# TAH_BOARD_VER_4_0.net
KiCad netlist of a schematic drawn in EAGLE
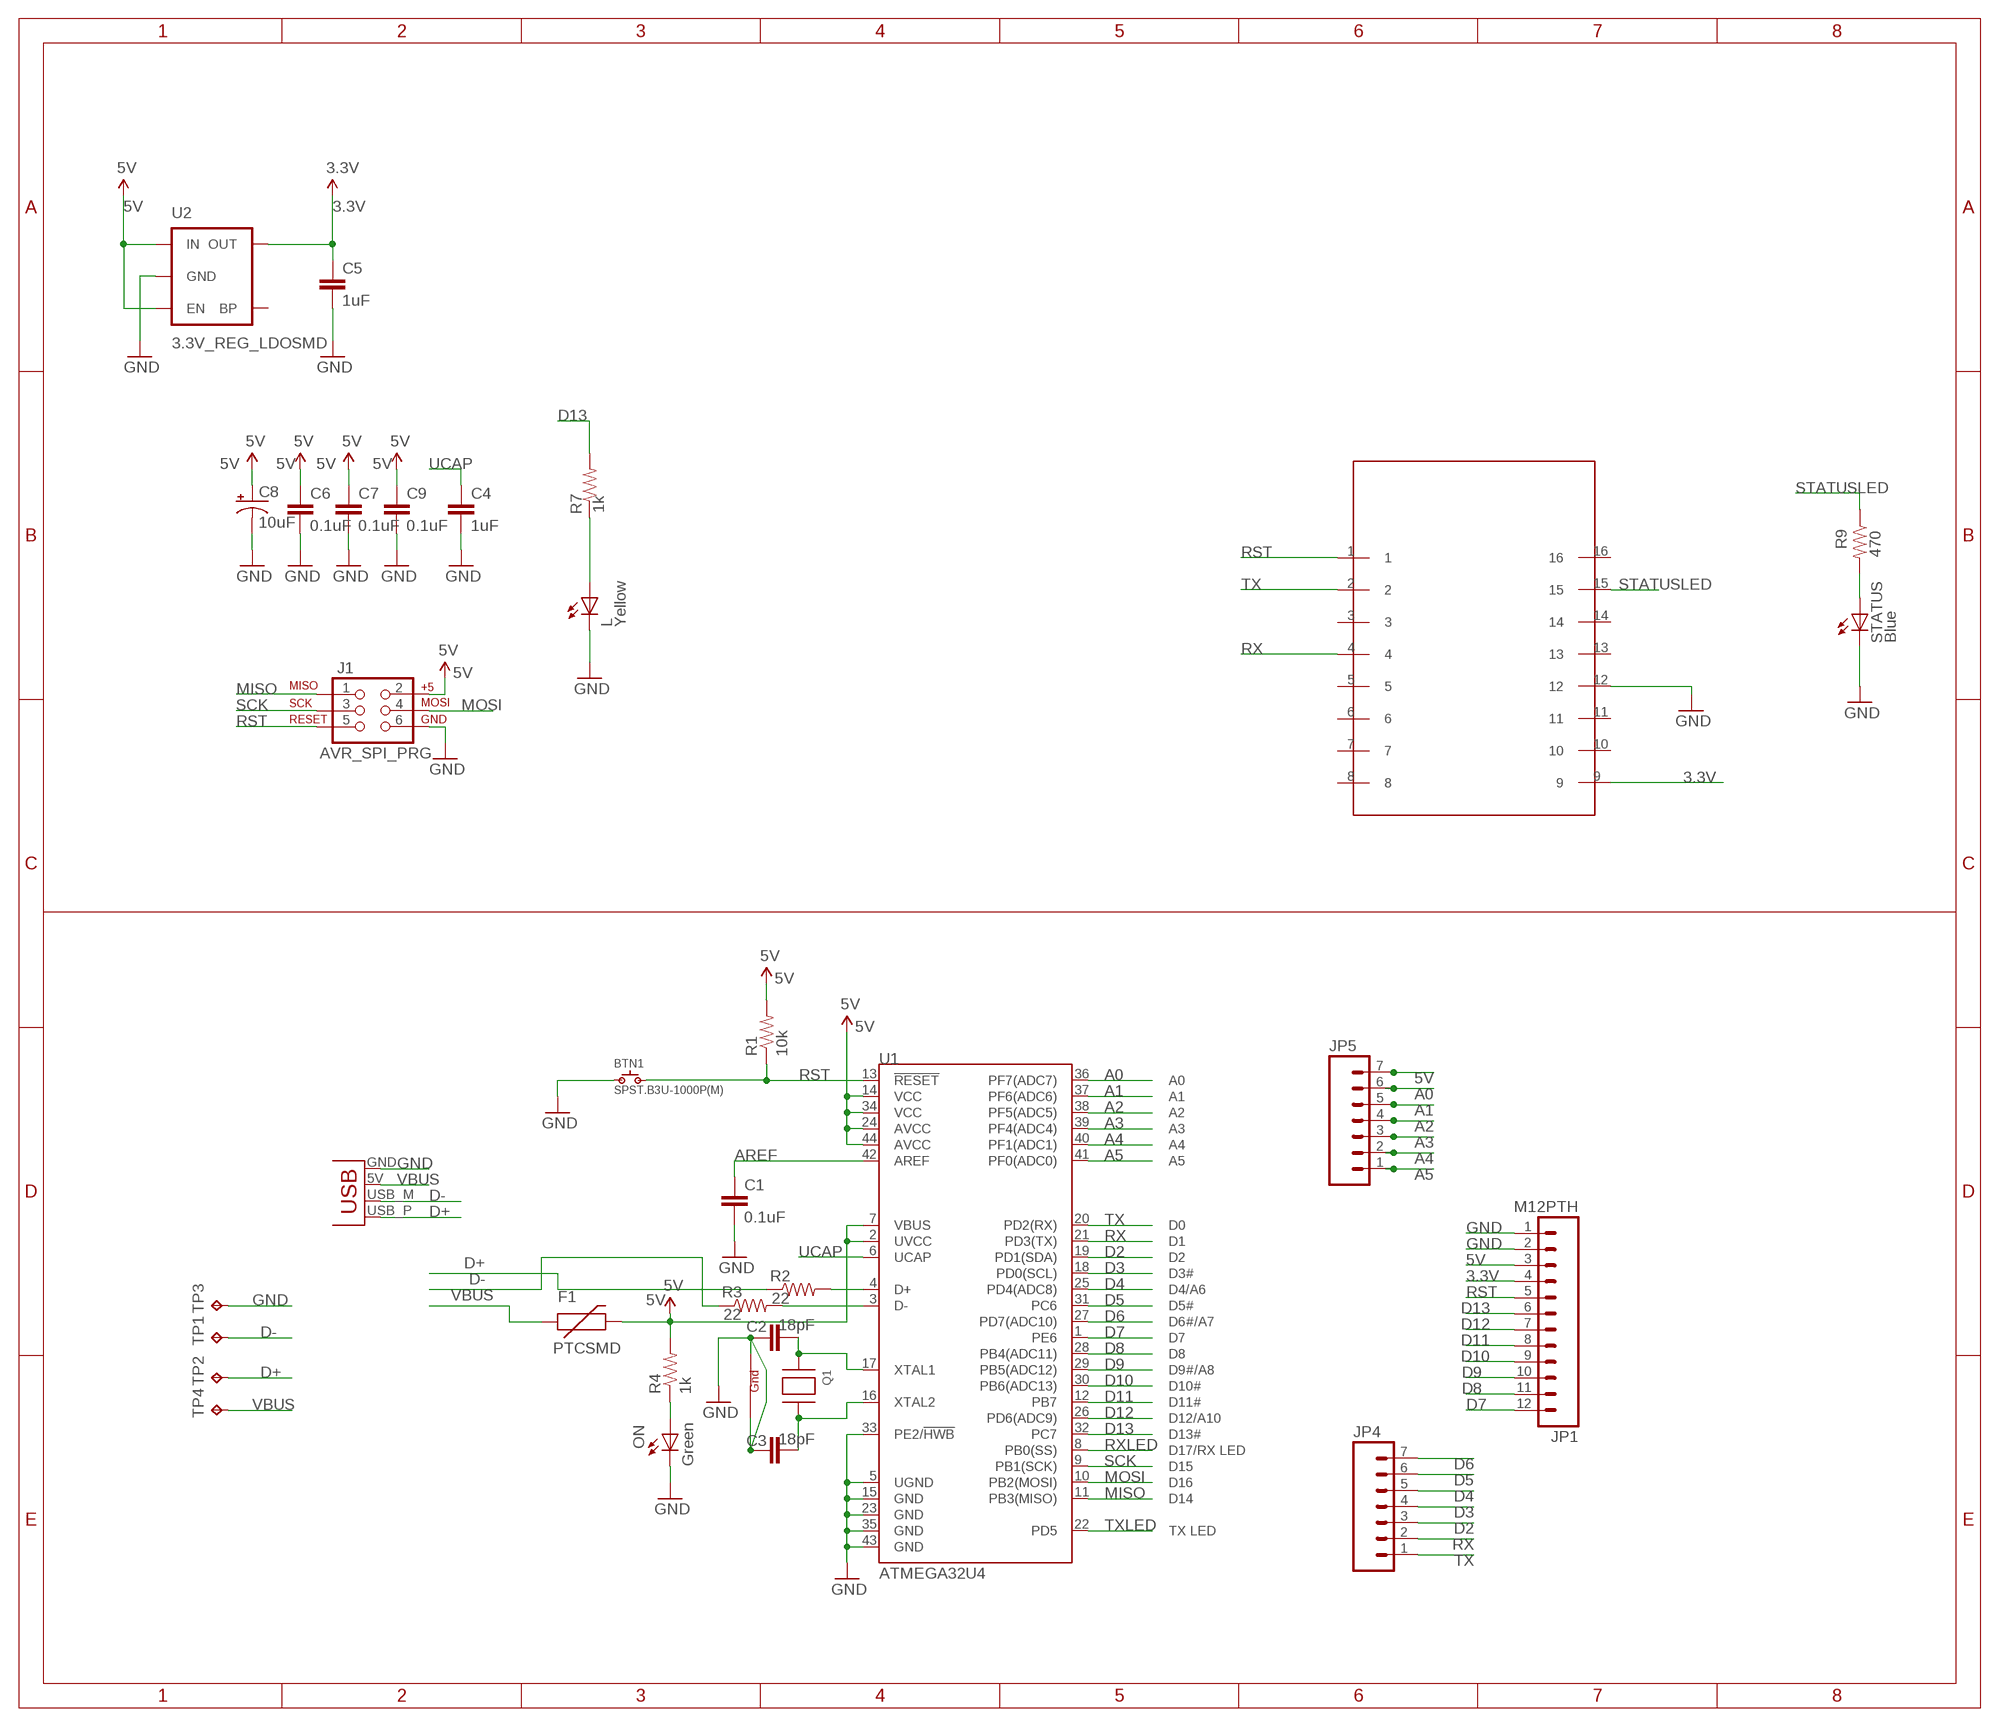
[diagram p0: schematic, sheet 1]

(export (version "E")
  (design (tool "Eeschema 10.0.6"))
  (components
    (comp (ref "BLE")
      (value "HM-11HM11")
      (footprint "eagle-import:BC05B-SMD")
      (libsource (lib "eagle-import") (part "HM-11HM11"))
    )
    (comp (ref "BTN1")
      (value "SPST.B3U-1000P(M)")
      (footprint "eagle-import:B3U-1000P(M)")
      (libsource (lib "eagle-import") (part "SPST.B3U-1000P(M)"))
    )
    (comp (ref "C1")
      (value "0.1uF")
      (footprint "eagle-import:1206")
      (libsource (lib "eagle-import") (part "2.2UF-CERCAP-10009"))
    )
    (comp (ref "C2")
      (value "18pF")
      (footprint "eagle-import:1206")
      (libsource (lib "eagle-import") (part "2.2UF-CERCAP-10009"))
    )
    (comp (ref "C3")
      (value "18pF")
      (footprint "eagle-import:1206")
      (libsource (lib "eagle-import") (part "2.2UF-CERCAP-10009"))
    )
    (comp (ref "C4")
      (value "1uF")
      (footprint "eagle-import:1206")
      (libsource (lib "eagle-import") (part "2.2UF-CERCAP-10009"))
    )
    (comp (ref "C5")
      (value "1uF")
      (footprint "eagle-import:1206")
      (libsource (lib "eagle-import") (part "2.2UF-CERCAP-10009"))
    )
    (comp (ref "C6")
      (value "0.1uF")
      (footprint "eagle-import:1206")
      (libsource (lib "eagle-import") (part "2.2UF-CERCAP-10009"))
    )
    (comp (ref "C7")
      (value "0.1uF")
      (footprint "eagle-import:1206")
      (libsource (lib "eagle-import") (part "2.2UF-CERCAP-10009"))
    )
    (comp (ref "C8")
      (value "10uF")
      (footprint "eagle-import:EIA3216")
      (libsource (lib "eagle-import") (part "CAP_POL1206"))
    )
    (comp (ref "C9")
      (value "0.1uF")
      (footprint "eagle-import:1206")
      (libsource (lib "eagle-import") (part "2.2UF-CERCAP-10009"))
    )
    (comp (ref "F1")
      (value "PTCSMD")
      (footprint "eagle-import:PTC-1206")
      (libsource (lib "eagle-import") (part "PTCSMD"))
    )
    (comp (ref "J1")
      (value "AVR_SPI_PRG")
      (footprint "eagle-import:2X3")
      (libsource (lib "eagle-import") (part "AVR_SPI_PRG_6PTH"))
    )
    (comp (ref "JP1")
      (value "M12PTH")
      (footprint "eagle-import:1X12")
      (libsource (lib "eagle-import") (part "M12PTH"))
    )
    (comp (ref "JP2")
      (value "USBPCB")
      (footprint "eagle-import:USB-A-PCB")
      (libsource (lib "eagle-import") (part "USBPCB"))
    )
    (comp (ref "JP4")
      (value "M07")
      (footprint "eagle-import:1X07")
      (libsource (lib "eagle-import") (part "M07"))
    )
    (comp (ref "JP5")
      (value "M07")
      (footprint "eagle-import:1X07")
      (libsource (lib "eagle-import") (part "M07"))
    )
    (comp (ref "L")
      (value "Yellow")
      (footprint "eagle-import:1206")
      (libsource (lib "eagle-import") (part "LEDSMT1206"))
    )
    (comp (ref "ON")
      (value "Green")
      (footprint "eagle-import:1206")
      (libsource (lib "eagle-import") (part "LEDSMT1206"))
    )
    (comp (ref "Q1")
      (value "XTAL-4-3225")
      (footprint "eagle-import:NX3225")
      (libsource (lib "eagle-import") (part "XTAL-4-3225"))
    )
    (comp (ref "R1")
      (value "10k")
      (footprint "eagle-import:1206")
      (libsource (lib "eagle-import") (part "RESISTOR1206"))
    )
    (comp (ref "R2")
      (value "22")
      (footprint "eagle-import:1206")
      (libsource (lib "eagle-import") (part "RESISTOR1206"))
    )
    (comp (ref "R3")
      (value "22")
      (footprint "eagle-import:1206")
      (libsource (lib "eagle-import") (part "RESISTOR1206"))
    )
    (comp (ref "R4")
      (value "1k")
      (footprint "eagle-import:1206")
      (libsource (lib "eagle-import") (part "RESISTOR1206"))
    )
    (comp (ref "R7")
      (value "1k")
      (footprint "eagle-import:1206")
      (libsource (lib "eagle-import") (part "RESISTOR1206"))
    )
    (comp (ref "R9")
      (value "470")
      (footprint "eagle-import:1206")
      (libsource (lib "eagle-import") (part "RESISTOR1206"))
    )
    (comp (ref "STATUS")
      (value "Blue")
      (footprint "eagle-import:1206")
      (libsource (lib "eagle-import") (part "LEDSMT1206"))
    )
    (comp (ref "TP1")
      (value "TPTP11SQ")
      (footprint "eagle-import:TP11SQ")
      (libsource (lib "eagle-import") (part "TPTP11SQ"))
    )
    (comp (ref "TP2")
      (value "TPTP11SQ")
      (footprint "eagle-import:TP11SQ")
      (libsource (lib "eagle-import") (part "TPTP11SQ"))
    )
    (comp (ref "TP3")
      (value "TPTP11SQ")
      (footprint "eagle-import:TP11SQ")
      (libsource (lib "eagle-import") (part "TPTP11SQ"))
    )
    (comp (ref "TP4")
      (value "TPTP11SQ")
      (footprint "eagle-import:TP11SQ")
      (libsource (lib "eagle-import") (part "TPTP11SQ"))
    )
    (comp (ref "U1")
      (value "ATMEGA32U4")
      (footprint "eagle-import:SPARKFUN-DIGITALIC_TQFP44")
      (libsource (lib "eagle-import") (part "ATMEGA32U4TQFP"))
    )
    (comp (ref "U2")
      (value "3.3V_REG_LDOSMD")
      (footprint "eagle-import:SOT23-5")
      (libsource (lib "eagle-import") (part "V_REG_LDOSMD"))
    )
  )
  (nets
    (net (code "1") (name "/A0") (class "Default")
      (node (ref "JP5") (pin "6") (pinfunction "6_6") (pintype "passive"))
      (node (ref "U1") (pin "36") (pinfunction "PF7(ADC7)_36") (pintype "bidirectional"))
    )
    (net (code "2") (name "/A1") (class "Default")
      (node (ref "JP5") (pin "5") (pinfunction "5_5") (pintype "passive"))
      (node (ref "U1") (pin "37") (pinfunction "PF6(ADC6)_37") (pintype "bidirectional"))
    )
    (net (code "3") (name "/A2") (class "Default")
      (node (ref "JP5") (pin "4") (pinfunction "4_4") (pintype "passive"))
      (node (ref "U1") (pin "38") (pinfunction "PF5(ADC5)_38") (pintype "bidirectional"))
    )
    (net (code "4") (name "/A3") (class "Default")
      (node (ref "JP5") (pin "3") (pinfunction "3_3") (pintype "passive"))
      (node (ref "U1") (pin "39") (pinfunction "PF4(ADC4)_39") (pintype "bidirectional"))
    )
    (net (code "5") (name "/A4") (class "Default")
      (node (ref "JP5") (pin "2") (pinfunction "2_2") (pintype "passive"))
      (node (ref "U1") (pin "40") (pinfunction "PF1(ADC1)_40") (pintype "bidirectional"))
    )
    (net (code "6") (name "/A5") (class "Default")
      (node (ref "JP5") (pin "1") (pinfunction "1_1") (pintype "passive"))
      (node (ref "U1") (pin "41") (pinfunction "PF0(ADC0)_41") (pintype "bidirectional"))
    )
    (net (code "7") (name "/AREF") (class "Default")
      (node (ref "C1") (pin "1") (pinfunction "1_1") (pintype "passive"))
      (node (ref "U1") (pin "42") (pinfunction "AREF_42") (pintype "bidirectional"))
    )
    (net (code "8") (name "/D+") (class "Default")
      (node (ref "JP2") (pin "USB_P") (pinfunction "D+_USB_P") (pintype "bidirectional"))
      (node (ref "R2") (pin "1") (pinfunction "1_1") (pintype "passive"))
      (node (ref "TP2") (pin "TP") (pinfunction "TP_TP") (pintype "input"))
    )
    (net (code "9") (name "/D-") (class "Default")
      (node (ref "JP2") (pin "USB_M") (pinfunction "D-_USB_M") (pintype "bidirectional"))
      (node (ref "R3") (pin "1") (pinfunction "1_1") (pintype "passive"))
      (node (ref "TP1") (pin "TP") (pinfunction "TP_TP") (pintype "input"))
    )
    (net (code "10") (name "/D2") (class "Default")
      (node (ref "JP4") (pin "3") (pinfunction "3_3") (pintype "passive"))
      (node (ref "U1") (pin "19") (pinfunction "PD1(SDA)_19") (pintype "bidirectional"))
    )
    (net (code "11") (name "/D3") (class "Default")
      (node (ref "JP4") (pin "4") (pinfunction "4_4") (pintype "passive"))
      (node (ref "U1") (pin "18") (pinfunction "PD0(SCL)_18") (pintype "bidirectional"))
    )
    (net (code "12") (name "/D4") (class "Default")
      (node (ref "JP4") (pin "5") (pinfunction "5_5") (pintype "passive"))
      (node (ref "U1") (pin "25") (pinfunction "PD4(ADC8)_25") (pintype "bidirectional"))
    )
    (net (code "13") (name "/D5") (class "Default")
      (node (ref "JP4") (pin "6") (pinfunction "6_6") (pintype "passive"))
      (node (ref "U1") (pin "31") (pinfunction "PC6_31") (pintype "bidirectional"))
    )
    (net (code "14") (name "/D6") (class "Default")
      (node (ref "JP4") (pin "7") (pinfunction "7_7") (pintype "passive"))
      (node (ref "U1") (pin "27") (pinfunction "PD7(ADC10)_27") (pintype "bidirectional"))
    )
    (net (code "15") (name "/D7") (class "Default")
      (node (ref "JP1") (pin "12") (pinfunction "12_12") (pintype "passive"))
      (node (ref "U1") (pin "1") (pinfunction "PE6_1") (pintype "bidirectional"))
    )
    (net (code "16") (name "/D8") (class "Default")
      (node (ref "JP1") (pin "11") (pinfunction "11_11") (pintype "passive"))
      (node (ref "U1") (pin "28") (pinfunction "PB4(ADC11)_28") (pintype "bidirectional"))
    )
    (net (code "17") (name "/D9") (class "Default")
      (node (ref "JP1") (pin "10") (pinfunction "10_10") (pintype "passive"))
      (node (ref "U1") (pin "29") (pinfunction "PB5(ADC12)_29") (pintype "bidirectional"))
    )
    (net (code "18") (name "/D10") (class "Default")
      (node (ref "JP1") (pin "9") (pinfunction "9_9") (pintype "passive"))
      (node (ref "U1") (pin "30") (pinfunction "PB6(ADC13)_30") (pintype "bidirectional"))
    )
    (net (code "19") (name "/D11") (class "Default")
      (node (ref "JP1") (pin "8") (pinfunction "8_8") (pintype "passive"))
      (node (ref "U1") (pin "12") (pinfunction "PB7_12") (pintype "bidirectional"))
    )
    (net (code "20") (name "/D12") (class "Default")
      (node (ref "JP1") (pin "7") (pinfunction "7_7") (pintype "passive"))
      (node (ref "U1") (pin "26") (pinfunction "PD6(ADC9)_26") (pintype "bidirectional"))
    )
    (net (code "21") (name "/D13") (class "Default")
      (node (ref "JP1") (pin "6") (pinfunction "6_6") (pintype "passive"))
      (node (ref "R7") (pin "2") (pinfunction "2_2") (pintype "passive"))
      (node (ref "U1") (pin "32") (pinfunction "PC7_32") (pintype "bidirectional"))
    )
    (net (code "22") (name "/MISO") (class "Default")
      (node (ref "J1") (pin "1") (pinfunction "1_1") (pintype "passive"))
      (node (ref "U1") (pin "11") (pinfunction "PB3(MISO)_11") (pintype "bidirectional"))
    )
    (net (code "23") (name "/MOSI") (class "Default")
      (node (ref "J1") (pin "4") (pinfunction "4_4") (pintype "passive"))
      (node (ref "U1") (pin "10") (pinfunction "PB2(MOSI)_10") (pintype "bidirectional"))
    )
    (net (code "24") (name "/RST") (class "Default")
      (node (ref "BLE") (pin "1") (pinfunction "1_1") (pintype "bidirectional"))
      (node (ref "BTN1") (pin "2") (pinfunction "2_2") (pintype "bidirectional"))
      (node (ref "J1") (pin "5") (pinfunction "5_5") (pintype "passive"))
      (node (ref "JP1") (pin "5") (pinfunction "5_5") (pintype "passive"))
      (node (ref "R1") (pin "1") (pinfunction "1_1") (pintype "passive"))
      (node (ref "U1") (pin "13") (pinfunction "~{RESET}_13") (pintype "bidirectional"))
    )
    (net (code "25") (name "/RX") (class "Default")
      (node (ref "BLE") (pin "4") (pinfunction "4_4") (pintype "bidirectional"))
      (node (ref "JP4") (pin "2") (pinfunction "2_2") (pintype "passive"))
      (node (ref "U1") (pin "21") (pinfunction "PD3(TX)_21") (pintype "bidirectional"))
    )
    (net (code "26") (name "/RXLED") (class "Default")
      (node (ref "U1") (pin "8") (pinfunction "PB0(SS)_8") (pintype "bidirectional"))
    )
    (net (code "27") (name "/SCK") (class "Default")
      (node (ref "J1") (pin "3") (pinfunction "3_3") (pintype "passive"))
      (node (ref "U1") (pin "9") (pinfunction "PB1(SCK)_9") (pintype "bidirectional"))
    )
    (net (code "28") (name "/STATUSLED") (class "Default")
      (node (ref "BLE") (pin "15") (pinfunction "15_15") (pintype "bidirectional"))
      (node (ref "R9") (pin "1") (pinfunction "1_1") (pintype "passive"))
    )
    (net (code "29") (name "/TX") (class "Default")
      (node (ref "BLE") (pin "2") (pinfunction "2_2") (pintype "bidirectional"))
      (node (ref "JP4") (pin "1") (pinfunction "1_1") (pintype "passive"))
      (node (ref "U1") (pin "20") (pinfunction "PD2(RX)_20") (pintype "bidirectional"))
    )
    (net (code "30") (name "/TXLED") (class "Default")
      (node (ref "U1") (pin "22") (pinfunction "PD5_22") (pintype "bidirectional"))
    )
    (net (code "31") (name "/UCAP") (class "Default")
      (node (ref "C4") (pin "1") (pinfunction "1_1") (pintype "passive"))
      (node (ref "U1") (pin "6") (pinfunction "UCAP_6") (pintype "bidirectional"))
    )
    (net (code "32") (name "/VBUS") (class "Default")
      (node (ref "F1") (pin "1") (pinfunction "1_1") (pintype "bidirectional"))
      (node (ref "JP2") (pin "5V") (pinfunction "VBUS_5V") (pintype "bidirectional"))
      (node (ref "TP4") (pin "TP") (pinfunction "TP_TP") (pintype "input"))
    )
    (net (code "33") (name "3.3V") (class "Default")
      (node (ref "BLE") (pin "9") (pinfunction "9_9") (pintype "bidirectional"))
      (node (ref "C5") (pin "1") (pinfunction "1_1") (pintype "passive"))
      (node (ref "JP1") (pin "4") (pinfunction "4_4") (pintype "passive"))
      (node (ref "U2") (pin "5") (pinfunction "OUT_5") (pintype "passive"))
    )
    (net (code "34") (name "5V") (class "Default")
      (node (ref "C6") (pin "1") (pinfunction "1_1") (pintype "passive"))
      (node (ref "C7") (pin "1") (pinfunction "1_1") (pintype "passive"))
      (node (ref "C8") (pin "A") (pinfunction "+_A") (pintype "passive"))
      (node (ref "C9") (pin "1") (pinfunction "1_1") (pintype "passive"))
      (node (ref "F1") (pin "2") (pinfunction "2_2") (pintype "bidirectional"))
      (node (ref "J1") (pin "2") (pinfunction "2_2") (pintype "passive"))
      (node (ref "JP1") (pin "3") (pinfunction "3_3") (pintype "passive"))
      (node (ref "JP5") (pin "7") (pinfunction "7_7") (pintype "passive"))
      (node (ref "R1") (pin "2") (pinfunction "2_2") (pintype "passive"))
      (node (ref "R4") (pin "2") (pinfunction "2_2") (pintype "passive"))
      (node (ref "U1") (pin "14") (pinfunction "VCC_14") (pintype "bidirectional"))
      (node (ref "U1") (pin "2") (pinfunction "UVCC_2") (pintype "bidirectional"))
      (node (ref "U1") (pin "24") (pinfunction "AVCC_24") (pintype "bidirectional"))
      (node (ref "U1") (pin "34") (pinfunction "VCC_34") (pintype "bidirectional"))
      (node (ref "U1") (pin "44") (pinfunction "AVCC_44") (pintype "bidirectional"))
      (node (ref "U1") (pin "7") (pinfunction "VBUS_7") (pintype "bidirectional"))
      (node (ref "U2") (pin "1") (pinfunction "IN_1") (pintype "input"))
      (node (ref "U2") (pin "3") (pinfunction "EN_3") (pintype "input"))
    )
    (net (code "35") (name "GND") (class "Default")
      (node (ref "BLE") (pin "12") (pinfunction "12_12") (pintype "bidirectional"))
      (node (ref "BTN1") (pin "1") (pinfunction "1_1") (pintype "bidirectional"))
      (node (ref "C1") (pin "2") (pinfunction "2_2") (pintype "passive"))
      (node (ref "C2") (pin "1") (pinfunction "1_1") (pintype "passive"))
      (node (ref "C3") (pin "1") (pinfunction "1_1") (pintype "passive"))
      (node (ref "C4") (pin "2") (pinfunction "2_2") (pintype "passive"))
      (node (ref "C5") (pin "2") (pinfunction "2_2") (pintype "passive"))
      (node (ref "C6") (pin "2") (pinfunction "2_2") (pintype "passive"))
      (node (ref "C7") (pin "2") (pinfunction "2_2") (pintype "passive"))
      (node (ref "C8") (pin "C") (pinfunction "-_C") (pintype "passive"))
      (node (ref "C9") (pin "2") (pinfunction "2_2") (pintype "passive"))
      (node (ref "J1") (pin "6") (pinfunction "6_6") (pintype "passive"))
      (node (ref "JP1") (pin "1") (pinfunction "1_1") (pintype "passive"))
      (node (ref "JP1") (pin "2") (pinfunction "2_2") (pintype "passive"))
      (node (ref "JP2") (pin "GND") (pinfunction "GND_GND") (pintype "bidirectional"))
      (node (ref "L") (pin "C") (pinfunction "C_C") (pintype "passive"))
      (node (ref "ON") (pin "C") (pinfunction "C_C") (pintype "passive"))
      (node (ref "Q1") (pin "2") (pinfunction "G2_2") (pintype "power_in"))
      (node (ref "Q1") (pin "4") (pinfunction "G1_4") (pintype "power_in"))
      (node (ref "STATUS") (pin "C") (pinfunction "C_C") (pintype "passive"))
      (node (ref "TP3") (pin "TP") (pinfunction "TP_TP") (pintype "input"))
      (node (ref "U1") (pin "15") (pinfunction "GND_15") (pintype "bidirectional"))
      (node (ref "U1") (pin "23") (pinfunction "GND_23") (pintype "bidirectional"))
      (node (ref "U1") (pin "33") (pinfunction "PE2/~{HWB}_33") (pintype "bidirectional"))
      (node (ref "U1") (pin "35") (pinfunction "GND_35") (pintype "bidirectional"))
      (node (ref "U1") (pin "43") (pinfunction "GND_43") (pintype "bidirectional"))
      (node (ref "U1") (pin "5") (pinfunction "UGND_5") (pintype "bidirectional"))
      (node (ref "U2") (pin "2") (pinfunction "GND_2") (pintype "input"))
    )
    (net (code "36") (name "Net-(L-PadA)") (class "Default")
      (node (ref "L") (pin "A") (pinfunction "A_A") (pintype "passive"))
      (node (ref "R7") (pin "1") (pinfunction "1_1") (pintype "passive"))
    )
    (net (code "37") (name "Net-(ON-PadA)") (class "Default")
      (node (ref "ON") (pin "A") (pinfunction "A_A") (pintype "passive"))
      (node (ref "R4") (pin "1") (pinfunction "1_1") (pintype "passive"))
    )
    (net (code "38") (name "Net-(Q1-X1)") (class "Default")
      (node (ref "C2") (pin "2") (pinfunction "2_2") (pintype "passive"))
      (node (ref "Q1") (pin "1") (pinfunction "X1_1") (pintype "bidirectional"))
      (node (ref "U1") (pin "17") (pinfunction "XTAL1_17") (pintype "bidirectional"))
    )
    (net (code "39") (name "Net-(Q1-X2)") (class "Default")
      (node (ref "C3") (pin "2") (pinfunction "2_2") (pintype "passive"))
      (node (ref "Q1") (pin "3") (pinfunction "X2_3") (pintype "bidirectional"))
      (node (ref "U1") (pin "16") (pinfunction "XTAL2_16") (pintype "bidirectional"))
    )
    (net (code "40") (name "Net-(R9-Pad2)") (class "Default")
      (node (ref "R9") (pin "2") (pinfunction "2_2") (pintype "passive"))
      (node (ref "STATUS") (pin "A") (pinfunction "A_A") (pintype "passive"))
    )
    (net (code "41") (name "Net-(U1-D+)") (class "Default")
      (node (ref "R2") (pin "2") (pinfunction "2_2") (pintype "passive"))
      (node (ref "U1") (pin "4") (pinfunction "D+_4") (pintype "bidirectional"))
    )
    (net (code "42") (name "Net-(U1-D-)") (class "Default")
      (node (ref "R3") (pin "2") (pinfunction "2_2") (pintype "passive"))
      (node (ref "U1") (pin "3") (pinfunction "D-_3") (pintype "bidirectional"))
    )
    (net (code "43") (name "unconnected-(BLE-Pad3)") (class "Default")
      (node (ref "BLE") (pin "3") (pinfunction "3_3") (pintype "bidirectional"))
    )
    (net (code "44") (name "unconnected-(BLE-Pad5)") (class "Default")
      (node (ref "BLE") (pin "5") (pinfunction "5_5") (pintype "bidirectional"))
    )
    (net (code "45") (name "unconnected-(BLE-Pad6)") (class "Default")
      (node (ref "BLE") (pin "6") (pinfunction "6_6") (pintype "bidirectional"))
    )
    (net (code "46") (name "unconnected-(BLE-Pad7)") (class "Default")
      (node (ref "BLE") (pin "7") (pinfunction "7_7") (pintype "bidirectional"))
    )
    (net (code "47") (name "unconnected-(BLE-Pad8)") (class "Default")
      (node (ref "BLE") (pin "8") (pinfunction "8_8") (pintype "bidirectional"))
    )
    (net (code "48") (name "unconnected-(BLE-Pad10)") (class "Default")
      (node (ref "BLE") (pin "10") (pinfunction "10_10") (pintype "bidirectional"))
    )
    (net (code "49") (name "unconnected-(BLE-Pad11)") (class "Default")
      (node (ref "BLE") (pin "11") (pinfunction "11_11") (pintype "bidirectional"))
    )
    (net (code "50") (name "unconnected-(BLE-Pad13)") (class "Default")
      (node (ref "BLE") (pin "13") (pinfunction "13_13") (pintype "bidirectional"))
    )
    (net (code "51") (name "unconnected-(BLE-Pad14)") (class "Default")
      (node (ref "BLE") (pin "14") (pinfunction "14_14") (pintype "bidirectional"))
    )
    (net (code "52") (name "unconnected-(BLE-Pad16)") (class "Default")
      (node (ref "BLE") (pin "16") (pinfunction "16_16") (pintype "bidirectional"))
    )
    (net (code "53") (name "unconnected-(U2-BP-Pad4)") (class "Default")
      (node (ref "U2") (pin "4") (pinfunction "BP_4") (pintype "input"))
    )
  )
)
